# Regulators_2.net
KiCad netlist of a schematic drawn in Altium Designer
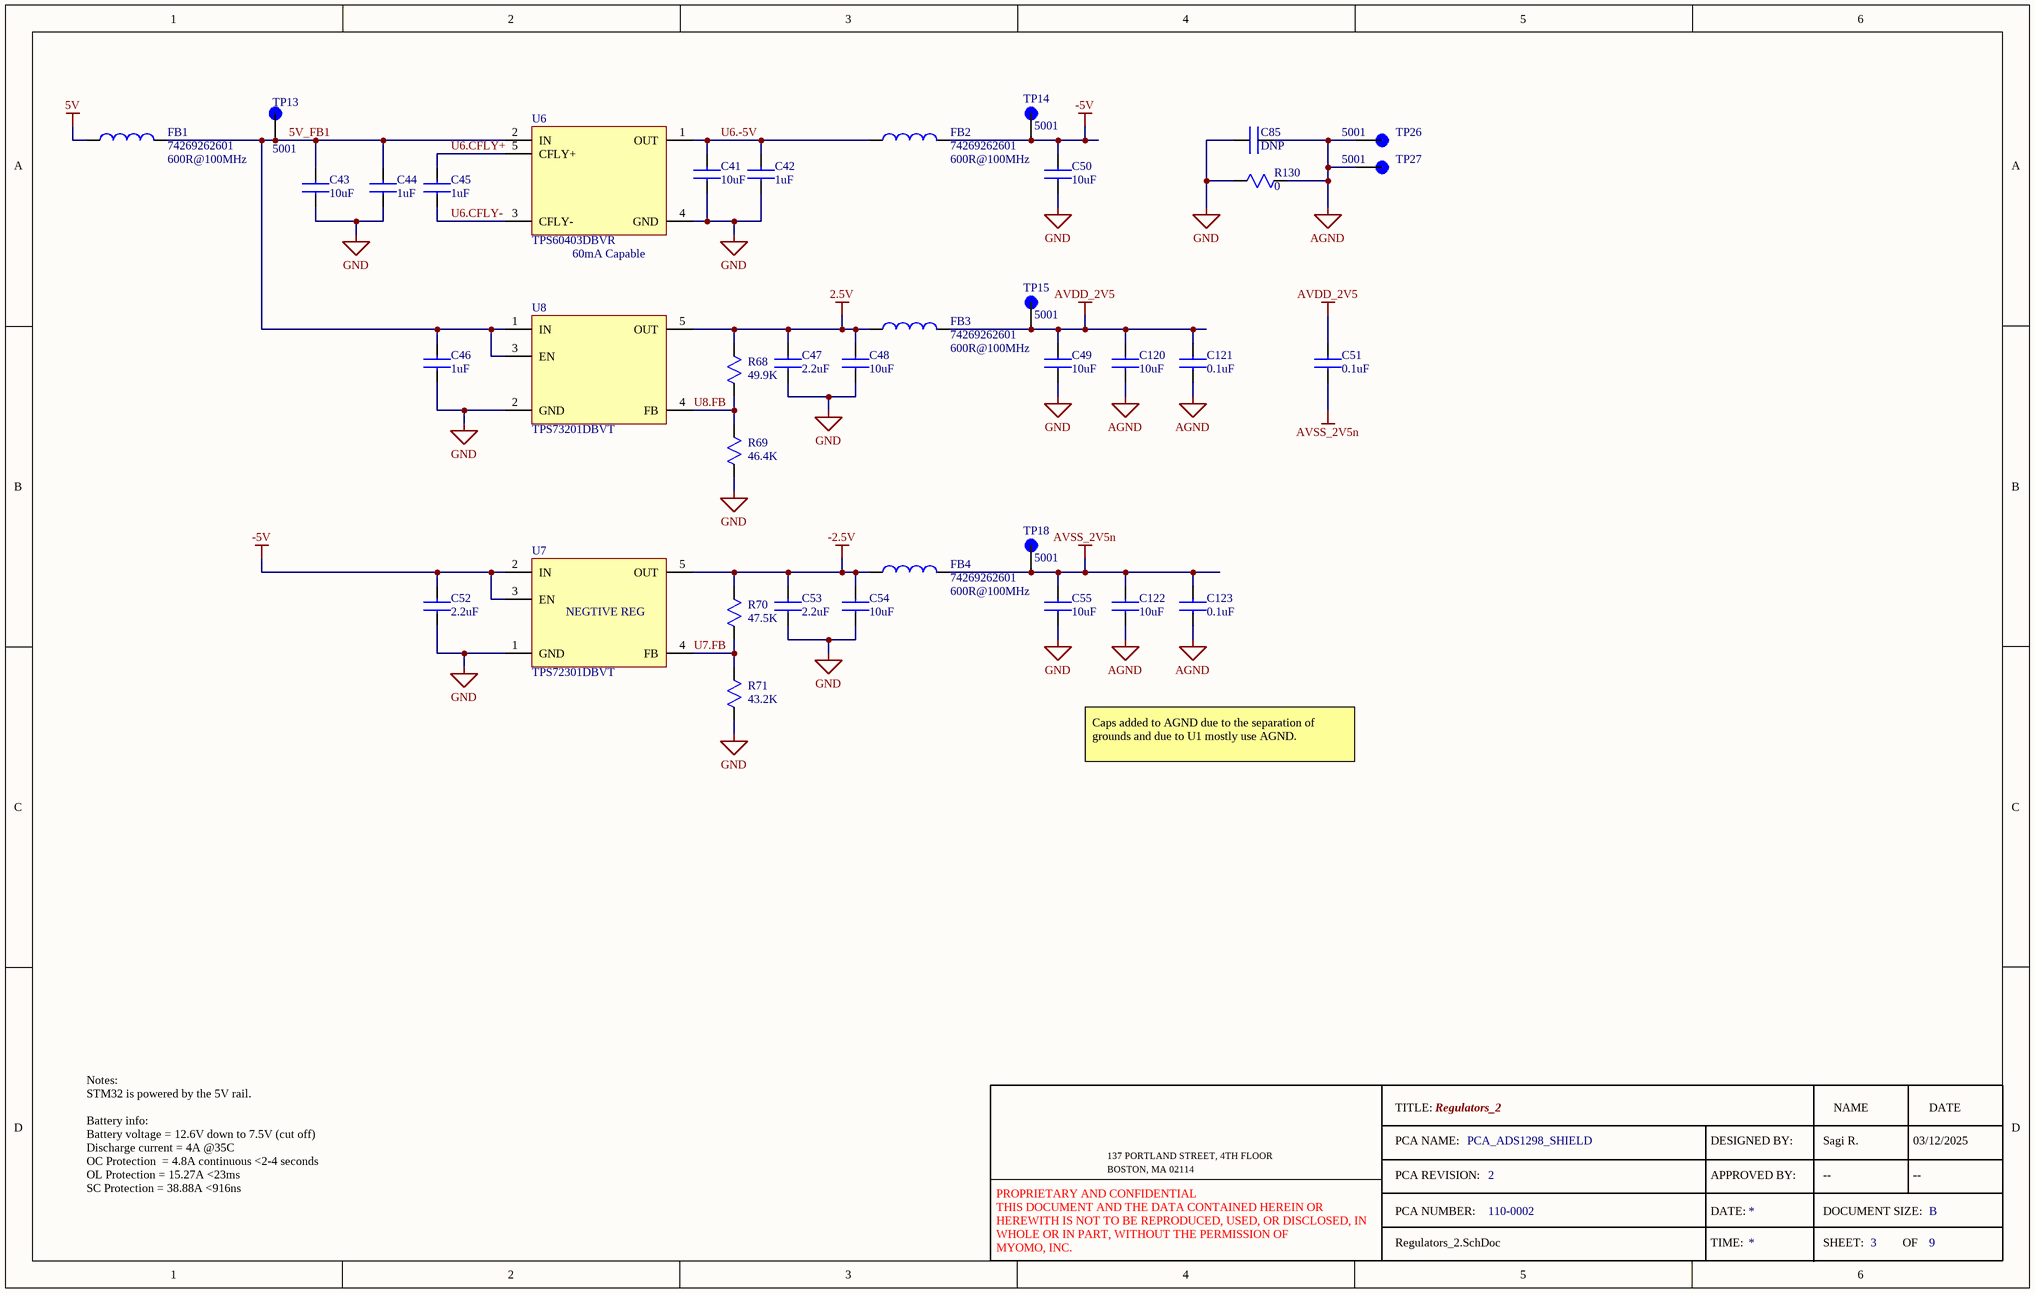
[diagram p0: Regulators_2.SchDoc]

(export (version "E")
  (design (tool "Eeschema 10.0.6"))
  (components
    (comp (ref "C41")
      (value "10uF")
      (footprint "1210")
      (description "CAP CER 10UF 25V X7R 1210")
      (fields (field (name "MFG") "SUMSUNG"))
      (libsource (lib "Myomo_SCH_Library") (part "C_1210_CER_10uF_25V_X7R"))
    )
    (comp (ref "C42")
      (value "1uF")
      (footprint "0603")
      (description "CAP CER 1UF 50V X7R 0603")
      (fields (field (name "MFG") "YAGEO"))
      (libsource (lib "Myomo_SCH_Library") (part "C_0603_CER_1uF_50V_X7R"))
    )
    (comp (ref "C43")
      (value "10uF")
      (footprint "1210")
      (description "CAP CER 10UF 25V X7R 1210")
      (fields (field (name "MFG") "SUMSUNG"))
      (libsource (lib "Myomo_SCH_Library") (part "C_1210_CER_10uF_25V_X7R"))
    )
    (comp (ref "C44")
      (value "1uF")
      (footprint "0603")
      (description "CAP CER 1UF 50V X7R 0603")
      (fields (field (name "MFG") "YAGEO"))
      (libsource (lib "Myomo_SCH_Library") (part "C_0603_CER_1uF_50V_X7R"))
    )
    (comp (ref "C45")
      (value "1uF")
      (footprint "0603")
      (description "CAP CER 1UF 50V X7R 0603")
      (fields (field (name "MFG") "YAGEO"))
      (libsource (lib "Myomo_SCH_Library") (part "C_0603_CER_1uF_50V_X7R"))
    )
    (comp (ref "C46")
      (value "1uF")
      (footprint "0603")
      (description "CAP CER 1UF 50V X7R 0603")
      (fields (field (name "MFG") "YAGEO"))
      (libsource (lib "Myomo_SCH_Library") (part "C_0603_CER_1uF_50V_X7R"))
    )
    (comp (ref "C47")
      (value "2.2uF")
      (footprint "0603")
      (description "CAP CER 2.2UF 50V X5R 0603")
      (fields (field (name "MFG") "SAMSUNG"))
      (libsource (lib "Myomo_SCH_Library") (part "C_0603_CER_2.2uF_50V_X5R"))
    )
    (comp (ref "C48")
      (value "10uF")
      (footprint "1210")
      (description "CAP CER 10UF 25V X7R 1210")
      (fields (field (name "MFG") "SUMSUNG"))
      (libsource (lib "Myomo_SCH_Library") (part "C_1210_CER_10uF_25V_X7R"))
    )
    (comp (ref "C49")
      (value "10uF")
      (footprint "1210")
      (description "CAP CER 10UF 25V X7R 1210")
      (fields (field (name "MFG") "SUMSUNG"))
      (libsource (lib "Myomo_SCH_Library") (part "C_1210_CER_10uF_25V_X7R"))
    )
    (comp (ref "C50")
      (value "10uF")
      (footprint "1210")
      (description "CAP CER 10UF 25V X7R 1210")
      (fields (field (name "MFG") "SUMSUNG"))
      (libsource (lib "Myomo_SCH_Library") (part "C_1210_CER_10uF_25V_X7R"))
    )
    (comp (ref "C51")
      (value "0.1uF")
      (footprint "0603")
      (description "CAP CER 0.1UF 100V X7R 0603")
      (fields (field (name "MFG") "SAMSUNG"))
      (libsource (lib "Myomo_SCH_Library") (part "C_0603_CER_0.1uF_100V_X7R"))
    )
    (comp (ref "C52")
      (value "2.2uF")
      (footprint "0603")
      (description "CAP CER 2.2UF 50V X5R 0603")
      (fields (field (name "MFG") "SAMSUNG"))
      (libsource (lib "Myomo_SCH_Library") (part "C_0603_CER_2.2uF_50V_X5R"))
    )
    (comp (ref "C53")
      (value "2.2uF")
      (footprint "0603")
      (description "CAP CER 2.2UF 50V X5R 0603")
      (fields (field (name "MFG") "SAMSUNG"))
      (libsource (lib "Myomo_SCH_Library") (part "C_0603_CER_2.2uF_50V_X5R"))
    )
    (comp (ref "C54")
      (value "10uF")
      (footprint "1210")
      (description "CAP CER 10UF 25V X7R 1210")
      (fields (field (name "MFG") "SUMSUNG"))
      (libsource (lib "Myomo_SCH_Library") (part "C_1210_CER_10uF_25V_X7R"))
    )
    (comp (ref "C55")
      (value "10uF")
      (footprint "1210")
      (description "CAP CER 10UF 25V X7R 1210")
      (fields (field (name "MFG") "SUMSUNG"))
      (libsource (lib "Myomo_SCH_Library") (part "C_1210_CER_10uF_25V_X7R"))
    )
    (comp (ref "C85")
      (value "DNP")
      (footprint "0603")
      (description "CAP CER 0603 DNP")
      (libsource (lib "Myomo_SCH_Library") (part "C_0603_DNP"))
    )
    (comp (ref "C120")
      (value "10uF")
      (footprint "1210")
      (description "CAP CER 10UF 25V X7R 1210")
      (fields (field (name "MFG") "SUMSUNG"))
      (libsource (lib "Myomo_SCH_Library") (part "C_1210_CER_10uF_25V_X7R"))
    )
    (comp (ref "C121")
      (value "0.1uF")
      (footprint "0603")
      (description "CAP CER 0.1UF 100V X7R 0603")
      (fields (field (name "MFG") "SAMSUNG"))
      (libsource (lib "Myomo_SCH_Library") (part "C_0603_CER_0.1uF_100V_X7R"))
    )
    (comp (ref "C122")
      (value "10uF")
      (footprint "1210")
      (description "CAP CER 10UF 25V X7R 1210")
      (fields (field (name "MFG") "SUMSUNG"))
      (libsource (lib "Myomo_SCH_Library") (part "C_1210_CER_10uF_25V_X7R"))
    )
    (comp (ref "C123")
      (value "0.1uF")
      (footprint "0603")
      (description "CAP CER 0.1UF 100V X7R 0603")
      (fields (field (name "MFG") "SAMSUNG"))
      (libsource (lib "Myomo_SCH_Library") (part "C_0603_CER_0.1uF_100V_X7R"))
    )
    (comp (ref "FB1")
      (value "74269262601")
      (footprint "0603")
      (description "600 Ohms @ 100 MHz 1 Power Line Ferrite Bead 0603 (1608 Metric) 1.5A 100mOhm")
      (fields (field (name "MFG") "Wurth Elektronik"))
      (libsource (lib "Myomo_SCH_Library") (part "FB_0603 _600_100MHz_1.5A"))
    )
    (comp (ref "FB2")
      (value "74269262601")
      (footprint "0603")
      (description "600 Ohms @ 100 MHz 1 Power Line Ferrite Bead 0603 (1608 Metric) 1.5A 100mOhm")
      (fields (field (name "MFG") "Wurth Elektronik"))
      (libsource (lib "Myomo_SCH_Library") (part "FB_0603 _600_100MHz_1.5A"))
    )
    (comp (ref "FB3")
      (value "74269262601")
      (footprint "0603")
      (description "600 Ohms @ 100 MHz 1 Power Line Ferrite Bead 0603 (1608 Metric) 1.5A 100mOhm")
      (fields (field (name "MFG") "Wurth Elektronik"))
      (libsource (lib "Myomo_SCH_Library") (part "FB_0603 _600_100MHz_1.5A"))
    )
    (comp (ref "FB4")
      (value "74269262601")
      (footprint "0603")
      (description "600 Ohms @ 100 MHz 1 Power Line Ferrite Bead 0603 (1608 Metric) 1.5A 100mOhm")
      (fields (field (name "MFG") "Wurth Elektronik"))
      (libsource (lib "Myomo_SCH_Library") (part "FB_0603 _600_100MHz_1.5A"))
    )
    (comp (ref "R68")
      (value "49.9K")
      (footprint "0603")
      (description "RES 49.9K OHM 1% 1/10W 0603")
      (fields (field (name "MFG") "YAGEO"))
      (libsource (lib "Myomo_SCH_Library") (part "R_0603_49.9K_1%_1/10W"))
    )
    (comp (ref "R69")
      (value "46.4K")
      (footprint "0603")
      (description "RES 46.4K OHM 1% 1/10W 0603")
      (fields (field (name "MFG") "YAGEO"))
      (libsource (lib "Myomo_SCH_Library") (part "R_0603_46.4K_1%_1/10W"))
    )
    (comp (ref "R70")
      (value "47.5K")
      (footprint "0603")
      (description "RES 47.5K OHM 1% 1/10W 0603")
      (fields (field (name "MFG") "YAGEO"))
      (libsource (lib "Myomo_SCH_Library") (part "R_0603_47.5K_1%_1/10W"))
    )
    (comp (ref "R71")
      (value "43.2K")
      (footprint "0603")
      (description "RES 43.2K OHM 1% 1/10W 0603")
      (fields (field (name "MFG") "YAGEO"))
      (libsource (lib "Myomo_SCH_Library") (part "R_0603_43.2K_1%_1/10W"))
    )
    (comp (ref "R130")
      (value "0")
      (footprint "0603")
      (description "RES 0 OHM JUMPER 1/10W 0603")
      (fields (field (name "MFG") "YAGEO"))
      (libsource (lib "Myomo_SCH_Library") (part "R_0603_0"))
    )
    (comp (ref "TP13")
      (value "5001")
      (footprint "TP_CLIP_BLK_5001")
      (description "PC TEST POINT MINIATURE BLACK")
      (fields (field (name "MFG") "Keystone Electronics"))
      (libsource (lib "Myomo_SCH_Library") (part "TP_CLIP_BLK_5001"))
    )
    (comp (ref "TP14")
      (value "5001")
      (footprint "TP_CLIP_BLK_5001")
      (description "PC TEST POINT MINIATURE BLACK")
      (fields (field (name "MFG") "Keystone Electronics"))
      (libsource (lib "Myomo_SCH_Library") (part "TP_CLIP_BLK_5001"))
    )
    (comp (ref "TP15")
      (value "5001")
      (footprint "TP_CLIP_BLK_5001")
      (description "PC TEST POINT MINIATURE BLACK")
      (fields (field (name "MFG") "Keystone Electronics"))
      (libsource (lib "Myomo_SCH_Library") (part "TP_CLIP_BLK_5001"))
    )
    (comp (ref "TP18")
      (value "5001")
      (footprint "TP_CLIP_BLK_5001")
      (description "PC TEST POINT MINIATURE BLACK")
      (fields (field (name "MFG") "Keystone Electronics"))
      (libsource (lib "Myomo_SCH_Library") (part "TP_CLIP_BLK_5001"))
    )
    (comp (ref "TP26")
      (value "5001")
      (footprint "TP_CLIP_BLK_5001")
      (description "PC TEST POINT MINIATURE BLACK")
      (fields (field (name "MFG") "Keystone Electronics"))
      (libsource (lib "Myomo_SCH_Library") (part "TP_CLIP_BLK_5001"))
    )
    (comp (ref "TP27")
      (value "5001")
      (footprint "TP_CLIP_BLK_5001")
      (description "PC TEST POINT MINIATURE BLACK")
      (fields (field (name "MFG") "Keystone Electronics"))
      (libsource (lib "Myomo_SCH_Library") (part "TP_CLIP_BLK_5001"))
    )
    (comp (ref "U6")
      (value "TPS60403DBVR")
      (footprint "U_TPS60403DBVR")
      (description "IC REG CHG PUMP INV 60MA SOT23-5")
      (fields (field (name "MFG") "TI"))
      (libsource (lib "Myomo_SCH_Library") (part "U_TPS60403DBVR"))
    )
    (comp (ref "U7")
      (value "TPS72301DBVT")
      (footprint "U_TPS72301DBVT_NEG")
      (description "IC REG LIN NEG ADJ 200MA SOT23-5")
      (fields (field (name "MFG") "TI"))
      (libsource (lib "Myomo_SCH_Library") (part "U_TPS72301DBVT_NEG"))
    )
    (comp (ref "U8")
      (value "TPS73201DBVT")
      (footprint "U_TPS73201DBVT")
      (description "IC REG LIN POS ADJ 250MA SOT23-5")
      (fields (field (name "MFG") "TI"))
      (libsource (lib "Myomo_SCH_Library") (part "U_TPS73201DBVT"))
    )
  )
  (nets
    (net (code "1") (name "-2.5V") (class "Default")
      (node (ref "C53") (pin "1") (pinfunction "1_1") (pintype "passive"))
      (node (ref "C54") (pin "1") (pinfunction "1_1") (pintype "passive"))
      (node (ref "FB4") (pin "1") (pinfunction "1_1") (pintype "passive"))
      (node (ref "R70") (pin "1") (pinfunction "1_1") (pintype "passive"))
      (node (ref "U7") (pin "5") (pinfunction "OUT_5") (pintype "power_in"))
    )
    (net (code "2") (name "-5V") (class "Default")
      (node (ref "C50") (pin "1") (pinfunction "1_1") (pintype "passive"))
      (node (ref "C52") (pin "1") (pinfunction "1_1") (pintype "passive"))
      (node (ref "FB2") (pin "2") (pinfunction "2_2") (pintype "passive"))
      (node (ref "TP14") (pin "TP") (pinfunction "TP_TP") (pintype "passive"))
      (node (ref "U7") (pin "2") (pinfunction "IN_2") (pintype "power_in"))
      (node (ref "U7") (pin "3") (pinfunction "EN_3") (pintype "power_in"))
    )
    (net (code "3") (name "/5V_FB1") (class "Default")
      (node (ref "C43") (pin "1") (pinfunction "1_1") (pintype "passive"))
      (node (ref "C44") (pin "1") (pinfunction "1_1") (pintype "passive"))
      (node (ref "C46") (pin "1") (pinfunction "1_1") (pintype "passive"))
      (node (ref "FB1") (pin "2") (pinfunction "2_2") (pintype "passive"))
      (node (ref "TP13") (pin "TP") (pinfunction "TP_TP") (pintype "passive"))
      (node (ref "U6") (pin "2") (pinfunction "IN_2") (pintype "power_in"))
      (node (ref "U8") (pin "1") (pinfunction "IN_1") (pintype "power_in"))
      (node (ref "U8") (pin "3") (pinfunction "EN_3") (pintype "power_in"))
    )
    (net (code "4") (name "/U6.-5V") (class "Default")
      (node (ref "C41") (pin "1") (pinfunction "1_1") (pintype "passive"))
      (node (ref "C42") (pin "1") (pinfunction "1_1") (pintype "passive"))
      (node (ref "FB2") (pin "1") (pinfunction "1_1") (pintype "passive"))
      (node (ref "U6") (pin "1") (pinfunction "OUT_1") (pintype "power_in"))
    )
    (net (code "5") (name "/U6.CFLY+") (class "Default")
      (node (ref "C45") (pin "1") (pinfunction "1_1") (pintype "passive"))
      (node (ref "U6") (pin "5") (pinfunction "CFLY+_5") (pintype "power_in"))
    )
    (net (code "6") (name "/U6.CFLY-") (class "Default")
      (node (ref "C45") (pin "2") (pinfunction "2_2") (pintype "passive"))
      (node (ref "U6") (pin "3") (pinfunction "CFLY-_3") (pintype "power_in"))
    )
    (net (code "7") (name "/U7.FB") (class "Default")
      (node (ref "R70") (pin "2") (pinfunction "2_2") (pintype "passive"))
      (node (ref "R71") (pin "1") (pinfunction "1_1") (pintype "passive"))
      (node (ref "U7") (pin "4") (pinfunction "FB_4") (pintype "power_in"))
    )
    (net (code "8") (name "/U8.FB") (class "Default")
      (node (ref "R68") (pin "2") (pinfunction "2_2") (pintype "passive"))
      (node (ref "R69") (pin "1") (pinfunction "1_1") (pintype "passive"))
      (node (ref "U8") (pin "4") (pinfunction "FB_4") (pintype "power_in"))
    )
    (net (code "9") (name "2.5V") (class "Default")
      (node (ref "C47") (pin "1") (pinfunction "1_1") (pintype "passive"))
      (node (ref "C48") (pin "1") (pinfunction "1_1") (pintype "passive"))
      (node (ref "FB3") (pin "1") (pinfunction "1_1") (pintype "passive"))
      (node (ref "R68") (pin "1") (pinfunction "1_1") (pintype "passive"))
      (node (ref "U8") (pin "5") (pinfunction "OUT_5") (pintype "power_in"))
    )
    (net (code "10") (name "5V") (class "Default")
      (node (ref "FB1") (pin "1") (pinfunction "1_1") (pintype "passive"))
    )
    (net (code "11") (name "AGND") (class "Default")
      (node (ref "C120") (pin "2") (pinfunction "2_2") (pintype "passive"))
      (node (ref "C121") (pin "2") (pinfunction "2_2") (pintype "passive"))
      (node (ref "C122") (pin "2") (pinfunction "2_2") (pintype "passive"))
      (node (ref "C123") (pin "2") (pinfunction "2_2") (pintype "passive"))
      (node (ref "C85") (pin "2") (pinfunction "2_2") (pintype "passive"))
      (node (ref "R130") (pin "2") (pinfunction "2_2") (pintype "passive"))
      (node (ref "TP26") (pin "TP") (pinfunction "TP_TP") (pintype "passive"))
      (node (ref "TP27") (pin "TP") (pinfunction "TP_TP") (pintype "passive"))
    )
    (net (code "12") (name "AVDD_2V5") (class "Default")
      (node (ref "C120") (pin "1") (pinfunction "1_1") (pintype "passive"))
      (node (ref "C121") (pin "1") (pinfunction "1_1") (pintype "passive"))
      (node (ref "C49") (pin "1") (pinfunction "1_1") (pintype "passive"))
      (node (ref "C51") (pin "1") (pinfunction "1_1") (pintype "passive"))
      (node (ref "FB3") (pin "2") (pinfunction "2_2") (pintype "passive"))
      (node (ref "TP15") (pin "TP") (pinfunction "TP_TP") (pintype "passive"))
    )
    (net (code "13") (name "AVSS_2V5n") (class "Default")
      (node (ref "C122") (pin "1") (pinfunction "1_1") (pintype "passive"))
      (node (ref "C123") (pin "1") (pinfunction "1_1") (pintype "passive"))
      (node (ref "C51") (pin "2") (pinfunction "2_2") (pintype "passive"))
      (node (ref "C55") (pin "1") (pinfunction "1_1") (pintype "passive"))
      (node (ref "FB4") (pin "2") (pinfunction "2_2") (pintype "passive"))
      (node (ref "TP18") (pin "TP") (pinfunction "TP_TP") (pintype "passive"))
    )
    (net (code "14") (name "GND") (class "Default")
      (node (ref "C41") (pin "2") (pinfunction "2_2") (pintype "passive"))
      (node (ref "C42") (pin "2") (pinfunction "2_2") (pintype "passive"))
      (node (ref "C43") (pin "2") (pinfunction "2_2") (pintype "passive"))
      (node (ref "C44") (pin "2") (pinfunction "2_2") (pintype "passive"))
      (node (ref "C46") (pin "2") (pinfunction "2_2") (pintype "passive"))
      (node (ref "C47") (pin "2") (pinfunction "2_2") (pintype "passive"))
      (node (ref "C48") (pin "2") (pinfunction "2_2") (pintype "passive"))
      (node (ref "C49") (pin "2") (pinfunction "2_2") (pintype "passive"))
      (node (ref "C50") (pin "2") (pinfunction "2_2") (pintype "passive"))
      (node (ref "C52") (pin "2") (pinfunction "2_2") (pintype "passive"))
      (node (ref "C53") (pin "2") (pinfunction "2_2") (pintype "passive"))
      (node (ref "C54") (pin "2") (pinfunction "2_2") (pintype "passive"))
      (node (ref "C55") (pin "2") (pinfunction "2_2") (pintype "passive"))
      (node (ref "C85") (pin "1") (pinfunction "1_1") (pintype "passive"))
      (node (ref "R130") (pin "1") (pinfunction "1_1") (pintype "passive"))
      (node (ref "R69") (pin "2") (pinfunction "2_2") (pintype "passive"))
      (node (ref "R71") (pin "2") (pinfunction "2_2") (pintype "passive"))
      (node (ref "U6") (pin "4") (pinfunction "GND_4") (pintype "power_in"))
      (node (ref "U7") (pin "1") (pinfunction "GND_1") (pintype "power_in"))
      (node (ref "U8") (pin "2") (pinfunction "GND_2") (pintype "power_in"))
    )
  )
)
